# Brain-PCB_Master.net
KiCad netlist of a schematic drawn in Altium Designer
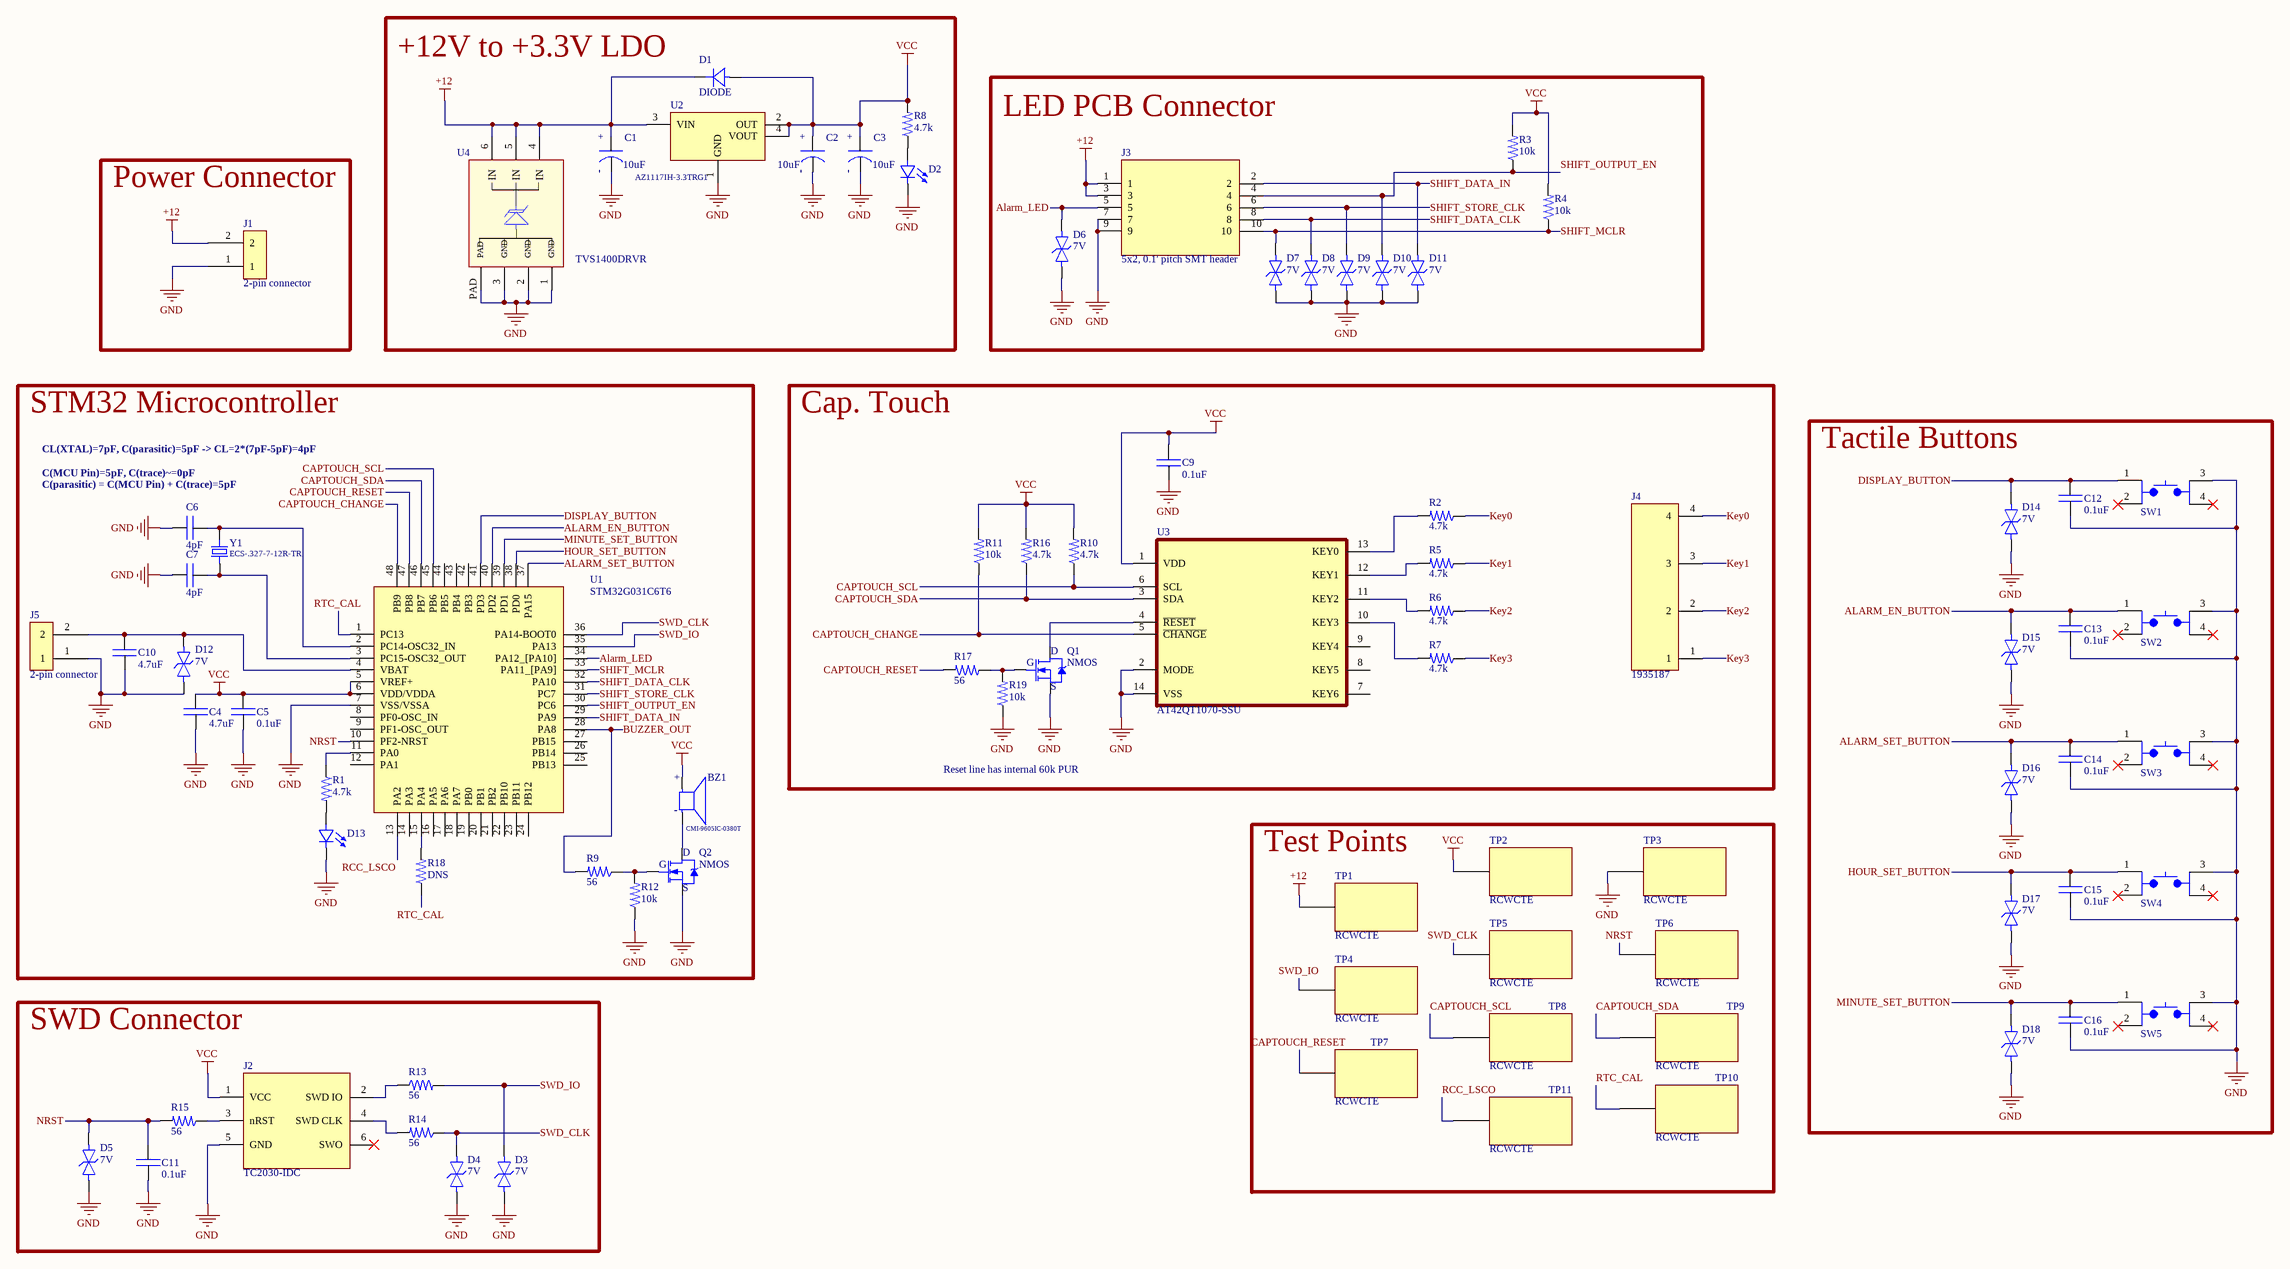
[diagram p0: Brain-PCB_Master.SchDoc]

(export (version "E")
  (design (tool "Eeschema 10.0.6"))
  (components
    (comp (ref "BZ1")
      (value "CMI-9605IC-0380T")
      (footprint "sinking-clock:CUI_CMI-9605IC-0380T")
      (description "MAGNETIC BUZZER INDICATOR")
      (fields (field (name "MFR") "CUI Devices"))
      (libsource (lib "sinking-clock") (part "CMI-9605IC-0380T"))
    )
    (comp (ref "C1")
      (value "10uF")
      (footprint "sinking-clock:CAP_CAN_POLY")
      (description "Capacitor")
      (fields (field (name "MFR") "Würth Elektronik") (field (name "Comment") "CAP"))
      (libsource (lib "sinking-clock") (part "CAP - POLARIZED"))
    )
    (comp (ref "C2")
      (value "10uF")
      (footprint "sinking-clock:CAP_CAN_POLY")
      (description "Capacitor")
      (fields (field (name "MFR") "Würth Elektronik") (field (name "Comment") "CAP"))
      (libsource (lib "sinking-clock") (part "CAP - POLARIZED"))
    )
    (comp (ref "C3")
      (value "10uF")
      (footprint "sinking-clock:CAP_CAN_POLY")
      (description "Capacitor")
      (fields (field (name "MFR") "Würth Elektronik") (field (name "Comment") "CAP"))
      (libsource (lib "sinking-clock") (part "CAP - POLARIZED"))
    )
    (comp (ref "C4")
      (value "4.7uF")
      (footprint "sinking-clock:0402C")
      (description "Capacitor")
      (fields (field (name "MFR") "Samsung Electro-Mechanics") (field (name "Comment") "CAP"))
      (libsource (lib "sinking-clock") (part "CAP"))
    )
    (comp (ref "C5")
      (value "0.1uF")
      (footprint "sinking-clock:0402C")
      (description "Capacitor")
      (fields (field (name "MFR") "Samsung Electro-Mechanics") (field (name "Comment") "CAP"))
      (libsource (lib "sinking-clock") (part "CAP"))
    )
    (comp (ref "C6")
      (value "4pF")
      (footprint "sinking-clock:0402C")
      (description "Capacitor")
      (fields (field (name "MFR") "YAGEO") (field (name "Comment") "CAP"))
      (libsource (lib "sinking-clock") (part "CAP"))
    )
    (comp (ref "C7")
      (value "4pF")
      (footprint "sinking-clock:0402C")
      (description "Capacitor")
      (fields (field (name "MFR") "YAGEO") (field (name "Comment") "CAP"))
      (libsource (lib "sinking-clock") (part "CAP"))
    )
    (comp (ref "C9")
      (value "0.1uF")
      (footprint "sinking-clock:0402C")
      (description "Capacitor")
      (fields (field (name "MFR") "Samsung Electro-Mechanics") (field (name "Comment") "CAP"))
      (libsource (lib "sinking-clock") (part "CAP"))
    )
    (comp (ref "C10")
      (value "4.7uF")
      (footprint "sinking-clock:0402C")
      (description "Capacitor")
      (fields (field (name "MFR") "Samsung Electro-Mechanics") (field (name "Comment") "CAP"))
      (libsource (lib "sinking-clock") (part "CAP"))
    )
    (comp (ref "C11")
      (value "0.1uF")
      (footprint "sinking-clock:0402C")
      (description "Capacitor")
      (fields (field (name "MFR") "Samsung Electro-Mechanics") (field (name "Comment") "CAP"))
      (libsource (lib "sinking-clock") (part "CAP"))
    )
    (comp (ref "C12")
      (value "0.1uF")
      (footprint "sinking-clock:0402C")
      (description "Capacitor")
      (fields (field (name "MFR") "Samsung Electro-Mechanics") (field (name "Comment") "CAP"))
      (libsource (lib "sinking-clock") (part "CAP"))
    )
    (comp (ref "C13")
      (value "0.1uF")
      (footprint "sinking-clock:0402C")
      (description "Capacitor")
      (fields (field (name "MFR") "Samsung Electro-Mechanics") (field (name "Comment") "CAP"))
      (libsource (lib "sinking-clock") (part "CAP"))
    )
    (comp (ref "C14")
      (value "0.1uF")
      (footprint "sinking-clock:0402C")
      (description "Capacitor")
      (fields (field (name "MFR") "Samsung Electro-Mechanics") (field (name "Comment") "CAP"))
      (libsource (lib "sinking-clock") (part "CAP"))
    )
    (comp (ref "C15")
      (value "0.1uF")
      (footprint "sinking-clock:0402C")
      (description "Capacitor")
      (fields (field (name "MFR") "Samsung Electro-Mechanics") (field (name "Comment") "CAP"))
      (libsource (lib "sinking-clock") (part "CAP"))
    )
    (comp (ref "C16")
      (value "0.1uF")
      (footprint "sinking-clock:0402C")
      (description "Capacitor")
      (fields (field (name "MFR") "Samsung Electro-Mechanics") (field (name "Comment") "CAP"))
      (libsource (lib "sinking-clock") (part "CAP"))
    )
    (comp (ref "D1")
      (value "DIODE")
      (footprint "sinking-clock:DO-214AC")
      (description "DIODE GEN PURP")
      (fields (field (name "MFR") "Micro Commercial Co"))
      (libsource (lib "sinking-clock") (part "DIODE"))
    )
    (comp (ref "D2")
      (value "LED - single")
      (footprint "sinking-clock:LED - 0603")
      (description "LED")
      (fields (field (name "MFR") "Dialight"))
      (libsource (lib "sinking-clock") (part "LED - single"))
    )
    (comp (ref "D3")
      (value "7V")
      (footprint "sinking-clock:DESD3V3S1BL-7B")
      (fields (field (name "MFR") "Diodes Incorporated"))
      (libsource (lib "sinking-clock") (part "TVS Diode Bi"))
    )
    (comp (ref "D4")
      (value "7V")
      (footprint "sinking-clock:DESD3V3S1BL-7B")
      (fields (field (name "MFR") "Diodes Incorporated"))
      (libsource (lib "sinking-clock") (part "TVS Diode Bi"))
    )
    (comp (ref "D5")
      (value "7V")
      (footprint "sinking-clock:DESD3V3S1BL-7B")
      (fields (field (name "MFR") "Diodes Incorporated"))
      (libsource (lib "sinking-clock") (part "TVS Diode Bi"))
    )
    (comp (ref "D6")
      (value "7V")
      (footprint "sinking-clock:DESD3V3S1BL-7B")
      (fields (field (name "MFR") "Diodes Incorporated"))
      (libsource (lib "sinking-clock") (part "TVS Diode Bi"))
    )
    (comp (ref "D7")
      (value "7V")
      (footprint "sinking-clock:DESD3V3S1BL-7B")
      (fields (field (name "MFR") "Diodes Incorporated"))
      (libsource (lib "sinking-clock") (part "TVS Diode Bi"))
    )
    (comp (ref "D8")
      (value "7V")
      (footprint "sinking-clock:DESD3V3S1BL-7B")
      (fields (field (name "MFR") "Diodes Incorporated"))
      (libsource (lib "sinking-clock") (part "TVS Diode Bi"))
    )
    (comp (ref "D9")
      (value "7V")
      (footprint "sinking-clock:DESD3V3S1BL-7B")
      (fields (field (name "MFR") "Diodes Incorporated"))
      (libsource (lib "sinking-clock") (part "TVS Diode Bi"))
    )
    (comp (ref "D10")
      (value "7V")
      (footprint "sinking-clock:DESD3V3S1BL-7B")
      (fields (field (name "MFR") "Diodes Incorporated"))
      (libsource (lib "sinking-clock") (part "TVS Diode Bi"))
    )
    (comp (ref "D11")
      (value "7V")
      (footprint "sinking-clock:DESD3V3S1BL-7B")
      (fields (field (name "MFR") "Diodes Incorporated"))
      (libsource (lib "sinking-clock") (part "TVS Diode Bi"))
    )
    (comp (ref "D12")
      (value "7V")
      (footprint "sinking-clock:DESD3V3S1BL-7B")
      (fields (field (name "MFR") "Diodes Incorporated"))
      (libsource (lib "sinking-clock") (part "TVS Diode Bi"))
    )
    (comp (ref "D13")
      (value "LED - single")
      (footprint "sinking-clock:LED - 0603")
      (description "LED")
      (fields (field (name "MFR") "Dialight"))
      (libsource (lib "sinking-clock") (part "LED - single"))
    )
    (comp (ref "D14")
      (value "7V")
      (footprint "sinking-clock:DESD3V3S1BL-7B")
      (fields (field (name "MFR") "Diodes Incorporated"))
      (libsource (lib "sinking-clock") (part "TVS Diode Bi"))
    )
    (comp (ref "D15")
      (value "7V")
      (footprint "sinking-clock:DESD3V3S1BL-7B")
      (fields (field (name "MFR") "Diodes Incorporated"))
      (libsource (lib "sinking-clock") (part "TVS Diode Bi"))
    )
    (comp (ref "D16")
      (value "7V")
      (footprint "sinking-clock:DESD3V3S1BL-7B")
      (fields (field (name "MFR") "Diodes Incorporated"))
      (libsource (lib "sinking-clock") (part "TVS Diode Bi"))
    )
    (comp (ref "D17")
      (value "7V")
      (footprint "sinking-clock:DESD3V3S1BL-7B")
      (fields (field (name "MFR") "Diodes Incorporated"))
      (libsource (lib "sinking-clock") (part "TVS Diode Bi"))
    )
    (comp (ref "D18")
      (value "7V")
      (footprint "sinking-clock:DESD3V3S1BL-7B")
      (fields (field (name "MFR") "Diodes Incorporated"))
      (libsource (lib "sinking-clock") (part "TVS Diode Bi"))
    )
    (comp (ref "J1")
      (value "2-pin connector")
      (footprint "sinking-clock:CONN_MOLEX_705510001")
      (description "CONN HEADER R/A 2POS 2.54MM")
      (fields (field (name "MFR") "MOLEX"))
      (libsource (lib "") (part "2-pin connector_1"))
    )
    (comp (ref "J2")
      (value "TC2030-IDC")
      (footprint "sinking-clock:TAG CONNECT TC2030IDC - NO 3D MODEL")
      (description "\"Plug of Nails\" POGO Pin connector")
      (fields (field (name "MFR") "Tag-Connect"))
      (libsource (lib "sinking-clock") (part "TC2030-IDC"))
    )
    (comp (ref "J3")
      (value "5x2, 0.1' pitch SMT header")
      (footprint "sinking-clock:5x2, 0.1' pitch SMT header")
      (description "CONN HEADER SMD 10POS 2.54MM")
      (fields (field (name "MFR") "CNC Tech"))
      (libsource (lib "sinking-clock") (part "5x2, 0.1' pitch SMT header"))
    )
    (comp (ref "J4")
      (value "1935187")
      (footprint "sinking-clock:1935187")
      (description "Fixed Terminal Blocks PT 1.5/4-5.0-H")
      (fields (field (name "MFR") "Phoenix Contact"))
      (libsource (lib "sinking-clock") (part "SCREW CONN 4 POS"))
    )
    (comp (ref "J5")
      (value "2-pin connector")
      (footprint "sinking-clock:CONN_MOLEX_705510001")
      (description "CONN HEADER R/A 2POS 2.54MM")
      (fields (field (name "MFR") "MOLEX"))
      (libsource (lib "sinking-clock") (part "2-pin connector"))
    )
    (comp (ref "Q1")
      (value "NMOS")
      (footprint "sinking-clock:SOT-23")
      (description "N-Channel MOSFET")
      (fields (field (name "MFR") "Diodes Incorporated"))
      (libsource (lib "sinking-clock") (part "NMOS"))
    )
    (comp (ref "Q2")
      (value "NMOS")
      (footprint "sinking-clock:SOT-23")
      (description "N-Channel MOSFET")
      (fields (field (name "MFR") "Diodes Incorporated"))
      (libsource (lib "sinking-clock") (part "NMOS"))
    )
    (comp (ref "R1")
      (value "4.7k")
      (footprint "sinking-clock:0402R")
      (description "Resistor")
      (fields (field (name "MFR") "YAGEO") (field (name "Comment") "RES"))
      (libsource (lib "sinking-clock") (part "RES"))
    )
    (comp (ref "R2")
      (value "4.7k")
      (footprint "sinking-clock:0402R")
      (description "Resistor")
      (fields (field (name "MFR") "YAGEO") (field (name "Comment") "RES"))
      (libsource (lib "sinking-clock") (part "RES"))
    )
    (comp (ref "R3")
      (value "10k")
      (footprint "sinking-clock:0402R")
      (description "Resistor")
      (fields (field (name "MFR") "YAGEO") (field (name "Comment") "RES"))
      (libsource (lib "sinking-clock") (part "RES"))
    )
    (comp (ref "R4")
      (value "10k")
      (footprint "sinking-clock:0402R")
      (description "Resistor")
      (fields (field (name "MFR") "YAGEO") (field (name "Comment") "RES"))
      (libsource (lib "sinking-clock") (part "RES"))
    )
    (comp (ref "R5")
      (value "4.7k")
      (footprint "sinking-clock:0402R")
      (description "Resistor")
      (fields (field (name "MFR") "YAGEO") (field (name "Comment") "RES"))
      (libsource (lib "sinking-clock") (part "RES"))
    )
    (comp (ref "R6")
      (value "4.7k")
      (footprint "sinking-clock:0402R")
      (description "Resistor")
      (fields (field (name "MFR") "YAGEO") (field (name "Comment") "RES"))
      (libsource (lib "sinking-clock") (part "RES"))
    )
    (comp (ref "R7")
      (value "4.7k")
      (footprint "sinking-clock:0402R")
      (description "Resistor")
      (fields (field (name "MFR") "YAGEO") (field (name "Comment") "RES"))
      (libsource (lib "sinking-clock") (part "RES"))
    )
    (comp (ref "R8")
      (value "4.7k")
      (footprint "sinking-clock:0402R")
      (description "Resistor")
      (fields (field (name "MFR") "YAGEO") (field (name "Comment") "RES"))
      (libsource (lib "sinking-clock") (part "RES"))
    )
    (comp (ref "R9")
      (value "56")
      (footprint "sinking-clock:0402R")
      (description "Resistor")
      (fields (field (name "MFR") "YAGEO") (field (name "Comment") "RES"))
      (libsource (lib "sinking-clock") (part "RES"))
    )
    (comp (ref "R10")
      (value "4.7k")
      (footprint "sinking-clock:0402R")
      (description "Resistor")
      (fields (field (name "MFR") "YAGEO") (field (name "Comment") "RES"))
      (libsource (lib "sinking-clock") (part "RES"))
    )
    (comp (ref "R11")
      (value "10k")
      (footprint "sinking-clock:0402R")
      (description "Resistor")
      (fields (field (name "MFR") "YAGEO") (field (name "Comment") "RES"))
      (libsource (lib "sinking-clock") (part "RES"))
    )
    (comp (ref "R12")
      (value "10k")
      (footprint "sinking-clock:0402R")
      (description "Resistor")
      (fields (field (name "MFR") "YAGEO") (field (name "Comment") "RES"))
      (libsource (lib "sinking-clock") (part "RES"))
    )
    (comp (ref "R13")
      (value "56")
      (footprint "sinking-clock:0402R")
      (description "Resistor")
      (fields (field (name "MFR") "YAGEO") (field (name "Comment") "RES"))
      (libsource (lib "sinking-clock") (part "RES"))
    )
    (comp (ref "R14")
      (value "56")
      (footprint "sinking-clock:0402R")
      (description "Resistor")
      (fields (field (name "MFR") "YAGEO") (field (name "Comment") "RES"))
      (libsource (lib "sinking-clock") (part "RES"))
    )
    (comp (ref "R15")
      (value "56")
      (footprint "sinking-clock:0402R")
      (description "Resistor")
      (fields (field (name "MFR") "YAGEO") (field (name "Comment") "RES"))
      (libsource (lib "sinking-clock") (part "RES"))
    )
    (comp (ref "R16")
      (value "4.7k")
      (footprint "sinking-clock:0402R")
      (description "Resistor")
      (fields (field (name "MFR") "YAGEO") (field (name "Comment") "RES"))
      (libsource (lib "sinking-clock") (part "RES"))
    )
    (comp (ref "R17")
      (value "56")
      (footprint "sinking-clock:0402R")
      (description "Resistor")
      (fields (field (name "MFR") "YAGEO") (field (name "Comment") "RES"))
      (libsource (lib "sinking-clock") (part "RES"))
    )
    (comp (ref "R18")
      (value "DNS")
      (footprint "sinking-clock:0402R")
      (description "Resistor")
      (fields (field (name "Comment") "RES"))
      (libsource (lib "sinking-clock") (part "RES"))
    )
    (comp (ref "R19")
      (value "10k")
      (footprint "sinking-clock:0402R")
      (description "Resistor")
      (fields (field (name "MFR") "YAGEO") (field (name "Comment") "RES"))
      (libsource (lib "sinking-clock") (part "RES"))
    )
    (comp (ref "SW1")
      (value "SPDT SMT Tactile Push Button Switch")
      (footprint "sinking-clock:TL3301BF160QGTUBE")
      (description "Tactile Push Button Switch, Gull Wing Lead, 9.5mm contact height")
      (fields (field (name "MFR") "E-Switch"))
      (libsource (lib "sinking-clock") (part "SPDT SMT Tactile Push Button Switch"))
    )
    (comp (ref "SW2")
      (value "SPDT SMT Tactile Push Button Switch")
      (footprint "sinking-clock:TL3301BF160QGTUBE")
      (description "Tactile Push Button Switch, Gull Wing Lead, 9.5mm contact height")
      (fields (field (name "MFR") "E-Switch"))
      (libsource (lib "sinking-clock") (part "SPDT SMT Tactile Push Button Switch"))
    )
    (comp (ref "SW3")
      (value "SPDT SMT Tactile Push Button Switch")
      (footprint "sinking-clock:TL3301BF160QGTUBE")
      (description "Tactile Push Button Switch, Gull Wing Lead, 9.5mm contact height")
      (fields (field (name "MFR") "E-Switch"))
      (libsource (lib "sinking-clock") (part "SPDT SMT Tactile Push Button Switch"))
    )
    (comp (ref "SW4")
      (value "SPDT SMT Tactile Push Button Switch")
      (footprint "sinking-clock:TL3301BF160QGTUBE")
      (description "Tactile Push Button Switch, Gull Wing Lead, 9.5mm contact height")
      (fields (field (name "MFR") "E-Switch"))
      (libsource (lib "sinking-clock") (part "SPDT SMT Tactile Push Button Switch"))
    )
    (comp (ref "SW5")
      (value "SPDT SMT Tactile Push Button Switch")
      (footprint "sinking-clock:TL3301BF160QGTUBE")
      (description "Tactile Push Button Switch, Gull Wing Lead, 9.5mm contact height")
      (fields (field (name "MFR") "E-Switch"))
      (libsource (lib "sinking-clock") (part "SPDT SMT Tactile Push Button Switch"))
    )
    (comp (ref "TP1")
      (value "RCWCTE")
      (footprint "sinking-clock:RCWCTE")
      (description "Test Point, Surface Mount")
      (fields (field (name "MFR") "KOA Speer Electronics, Inc."))
      (libsource (lib "sinking-clock") (part "Test Point"))
    )
    (comp (ref "TP2")
      (value "RCWCTE")
      (footprint "sinking-clock:RCWCTE")
      (description "Test Point, Surface Mount")
      (fields (field (name "MFR") "KOA Speer Electronics, Inc."))
      (libsource (lib "sinking-clock") (part "Test Point"))
    )
    (comp (ref "TP3")
      (value "RCWCTE")
      (footprint "sinking-clock:RCWCTE")
      (description "Test Point, Surface Mount")
      (fields (field (name "MFR") "KOA Speer Electronics, Inc."))
      (libsource (lib "sinking-clock") (part "Test Point"))
    )
    (comp (ref "TP4")
      (value "RCWCTE")
      (footprint "sinking-clock:RCWCTE")
      (description "Test Point, Surface Mount")
      (fields (field (name "MFR") "KOA Speer Electronics, Inc."))
      (libsource (lib "sinking-clock") (part "Test Point"))
    )
    (comp (ref "TP5")
      (value "RCWCTE")
      (footprint "sinking-clock:RCWCTE")
      (description "Test Point, Surface Mount")
      (fields (field (name "MFR") "KOA Speer Electronics, Inc."))
      (libsource (lib "sinking-clock") (part "Test Point"))
    )
    (comp (ref "TP6")
      (value "RCWCTE")
      (footprint "sinking-clock:RCWCTE")
      (description "Test Point, Surface Mount")
      (fields (field (name "MFR") "KOA Speer Electronics, Inc."))
      (libsource (lib "sinking-clock") (part "Test Point"))
    )
    (comp (ref "TP7")
      (value "RCWCTE")
      (footprint "sinking-clock:RCWCTE")
      (description "Test Point, Surface Mount")
      (fields (field (name "MFR") "KOA Speer Electronics, Inc."))
      (libsource (lib "sinking-clock") (part "Test Point"))
    )
    (comp (ref "TP8")
      (value "RCWCTE")
      (footprint "sinking-clock:RCWCTE")
      (description "Test Point, Surface Mount")
      (fields (field (name "MFR") "KOA Speer Electronics, Inc."))
      (libsource (lib "sinking-clock") (part "Test Point"))
    )
    (comp (ref "TP9")
      (value "RCWCTE")
      (footprint "sinking-clock:RCWCTE")
      (description "Test Point, Surface Mount")
      (fields (field (name "MFR") "KOA Speer Electronics, Inc."))
      (libsource (lib "sinking-clock") (part "Test Point"))
    )
    (comp (ref "TP10")
      (value "RCWCTE")
      (footprint "sinking-clock:RCWCTE")
      (description "Test Point, Surface Mount")
      (fields (field (name "MFR") "KOA Speer Electronics, Inc."))
      (libsource (lib "sinking-clock") (part "Test Point"))
    )
    (comp (ref "TP11")
      (value "RCWCTE")
      (footprint "sinking-clock:RCWCTE")
      (description "Test Point, Surface Mount")
      (fields (field (name "MFR") "KOA Speer Electronics, Inc."))
      (libsource (lib "sinking-clock") (part "Test Point"))
    )
    (comp (ref "U1")
      (value "STM32G031C6T6")
      (footprint "sinking-clock:48-LQFP")
      (fields (field (name "MFR") "STMicroelectronics"))
      (libsource (lib "sinking-clock") (part "STM32G031C6T6"))
    )
    (comp (ref "U2")
      (value "AZ1117IH-3.3TRG1")
      (footprint "sinking-clock:SOT-223-3")
      (description "IC REG LINEAR 3.3V 1A SOT223")
      (fields (field (name "MFR") "Diodes Incorporated"))
      (libsource (lib "sinking-clock") (part "AZ1117IH-3.3TRG1"))
    )
    (comp (ref "U3")
      (value "AT42QT1070-SSU")
      (footprint "sinking-clock:14-SOIC")
      (description "Capacitive Touch Buttons 14-SOIC")
      (fields (field (name "MFR") "Microchip"))
      (libsource (lib "sinking-clock") (part "AT42QT1070-SSU"))
    )
    (comp (ref "U4")
      (value "TVS1400DRVR")
      (footprint "sinking-clock:6-WDFN-EP")
      (description "UNIDIR  PRECISION SURGE DIODE")
      (fields (field (name "MFR") "Texas Instruments"))
      (libsource (lib "sinking-clock") (part "TVS1400DRVR"))
    )
    (comp (ref "Y1")
      (value "ECS-.327-7-12R-TR")
      (footprint "sinking-clock:ECS-.327-12.5-12R-TR")
      (description "SMD Tuning Fork Crystal")
      (fields (field (name "MFR") "ECS Inc."))
      (libsource (lib "sinking-clock") (part "ECS-.327-7-12R-TR"))
    )
  )
  (nets
    (net (code "1") (name "+12") (class "Default")
      (node (ref "C1") (pin "1") (pinfunction "1_1") (pintype "passive"))
      (node (ref "D1") (pin "K") (pinfunction "K_K") (pintype "passive"))
      (node (ref "J1") (pin "2") (pinfunction "2_2") (pintype "passive"))
      (node (ref "J3") (pin "1") (pinfunction "1_1") (pintype "passive"))
      (node (ref "J3") (pin "3") (pinfunction "3_3") (pintype "passive"))
      (node (ref "TP1") (pin "1") (pinfunction "0_1") (pintype "passive"))
      (node (ref "U2") (pin "3") (pinfunction "VIN_3") (pintype "passive"))
      (node (ref "U4") (pin "4") (pinfunction "IN_4") (pintype "passive"))
      (node (ref "U4") (pin "5") (pinfunction "IN_5") (pintype "passive"))
      (node (ref "U4") (pin "6") (pinfunction "IN_6") (pintype "passive"))
    )
    (net (code "2") (name "/ALARM_EN_BUTTON") (class "Default")
      (node (ref "C13") (pin "2") (pinfunction "2_2") (pintype "passive"))
      (node (ref "D15") (pin "1") (pinfunction "1_1") (pintype "passive"))
      (node (ref "SW2") (pin "1") (pinfunction "1_1") (pintype "passive"))
      (node (ref "U1") (pin "40") (pinfunction "PD2_40") (pintype "passive"))
    )
    (net (code "3") (name "/ALARM_SET_BUTTON") (class "Default")
      (node (ref "C14") (pin "2") (pinfunction "2_2") (pintype "passive"))
      (node (ref "D16") (pin "1") (pinfunction "1_1") (pintype "passive"))
      (node (ref "SW3") (pin "1") (pinfunction "1_1") (pintype "passive"))
      (node (ref "U1") (pin "37") (pinfunction "PA15_37") (pintype "passive"))
    )
    (net (code "4") (name "/Alarm_LED") (class "Default")
      (node (ref "D6") (pin "1") (pinfunction "1_1") (pintype "passive"))
      (node (ref "J3") (pin "5") (pinfunction "5_5") (pintype "passive"))
      (node (ref "U1") (pin "34") (pinfunction "PA12_[PA10]_34") (pintype "passive"))
    )
    (net (code "5") (name "/BUZZER_OUT") (class "Default")
      (node (ref "R9") (pin "2") (pinfunction "2_2") (pintype "passive"))
      (node (ref "U1") (pin "28") (pinfunction "PA8_28") (pintype "passive"))
    )
    (net (code "6") (name "/CAPTOUCH_CHANGE") (class "Default")
      (node (ref "R11") (pin "1") (pinfunction "1_1") (pintype "passive"))
      (node (ref "U1") (pin "48") (pinfunction "PB9_48") (pintype "passive"))
      (node (ref "U3") (pin "5") (pinfunction "~{CHANGE}_5") (pintype "passive"))
    )
    (net (code "7") (name "/CAPTOUCH_RESET") (class "Default")
      (node (ref "R17") (pin "2") (pinfunction "2_2") (pintype "passive"))
      (node (ref "TP7") (pin "1") (pinfunction "0_1") (pintype "passive"))
      (node (ref "U1") (pin "47") (pinfunction "PB8_47") (pintype "passive"))
    )
    (net (code "8") (name "/CAPTOUCH_SCL") (class "Default")
      (node (ref "R10") (pin "1") (pinfunction "1_1") (pintype "passive"))
      (node (ref "TP8") (pin "1") (pinfunction "0_1") (pintype "passive"))
      (node (ref "U1") (pin "45") (pinfunction "PB6_45") (pintype "passive"))
      (node (ref "U3") (pin "6") (pinfunction "SCL_6") (pintype "passive"))
    )
    (net (code "9") (name "/CAPTOUCH_SDA") (class "Default")
      (node (ref "R16") (pin "1") (pinfunction "1_1") (pintype "passive"))
      (node (ref "TP9") (pin "1") (pinfunction "0_1") (pintype "passive"))
      (node (ref "U1") (pin "46") (pinfunction "PB7_46") (pintype "passive"))
      (node (ref "U3") (pin "3") (pinfunction "SDA_3") (pintype "passive"))
    )
    (net (code "10") (name "/DISPLAY_BUTTON") (class "Default")
      (node (ref "C12") (pin "2") (pinfunction "2_2") (pintype "passive"))
      (node (ref "D14") (pin "1") (pinfunction "1_1") (pintype "passive"))
      (node (ref "SW1") (pin "1") (pinfunction "1_1") (pintype "passive"))
      (node (ref "U1") (pin "41") (pinfunction "PD3_41") (pintype "passive"))
    )
    (net (code "11") (name "/HOUR_SET_BUTTON") (class "Default")
      (node (ref "C15") (pin "2") (pinfunction "2_2") (pintype "passive"))
      (node (ref "D17") (pin "1") (pinfunction "1_1") (pintype "passive"))
      (node (ref "SW4") (pin "1") (pinfunction "1_1") (pintype "passive"))
      (node (ref "U1") (pin "38") (pinfunction "PD0_38") (pintype "passive"))
    )
    (net (code "12") (name "/Key0") (class "Default")
      (node (ref "J4") (pin "4") (pinfunction "4_4") (pintype "passive"))
      (node (ref "R2") (pin "1") (pinfunction "1_1") (pintype "passive"))
    )
    (net (code "13") (name "/Key1") (class "Default")
      (node (ref "J4") (pin "3") (pinfunction "3_3") (pintype "passive"))
      (node (ref "R5") (pin "1") (pinfunction "1_1") (pintype "passive"))
    )
    (net (code "14") (name "/Key2") (class "Default")
      (node (ref "J4") (pin "2") (pinfunction "2_2") (pintype "passive"))
      (node (ref "R6") (pin "1") (pinfunction "1_1") (pintype "passive"))
    )
    (net (code "15") (name "/Key3") (class "Default")
      (node (ref "J4") (pin "1") (pinfunction "1_1") (pintype "passive"))
      (node (ref "R7") (pin "1") (pinfunction "1_1") (pintype "passive"))
    )
    (net (code "16") (name "/MINUTE_SET_BUTTON") (class "Default")
      (node (ref "C16") (pin "2") (pinfunction "2_2") (pintype "passive"))
      (node (ref "D18") (pin "1") (pinfunction "1_1") (pintype "passive"))
      (node (ref "SW5") (pin "1") (pinfunction "1_1") (pintype "passive"))
      (node (ref "U1") (pin "39") (pinfunction "PD1_39") (pintype "passive"))
    )
    (net (code "17") (name "/NRST") (class "Default")
      (node (ref "C11") (pin "2") (pinfunction "2_2") (pintype "passive"))
      (node (ref "D5") (pin "1") (pinfunction "1_1") (pintype "passive"))
      (node (ref "R15") (pin "2") (pinfunction "2_2") (pintype "passive"))
      (node (ref "TP6") (pin "1") (pinfunction "0_1") (pintype "passive"))
      (node (ref "U1") (pin "10") (pinfunction "PF2-NRST_10") (pintype "passive"))
    )
    (net (code "18") (name "/RCC_LSCO") (class "Default")
      (node (ref "TP11") (pin "1") (pinfunction "0_1") (pintype "passive"))
      (node (ref "U1") (pin "13") (pinfunction "PA2_13") (pintype "passive"))
    )
    (net (code "19") (name "/RTC_CAL") (class "Default")
      (node (ref "R18") (pin "1") (pinfunction "1_1") (pintype "passive"))
      (node (ref "TP10") (pin "1") (pinfunction "0_1") (pintype "passive"))
      (node (ref "U1") (pin "1") (pinfunction "PC13_1") (pintype "passive"))
    )
    (net (code "20") (name "/SHIFT_DATA_CLK") (class "Default")
      (node (ref "D8") (pin "1") (pinfunction "1_1") (pintype "passive"))
      (node (ref "J3") (pin "8") (pinfunction "8_8") (pintype "passive"))
      (node (ref "U1") (pin "32") (pinfunction "PA10_32") (pintype "passive"))
    )
    (net (code "21") (name "/SHIFT_DATA_IN") (class "Default")
      (node (ref "D11") (pin "1") (pinfunction "1_1") (pintype "passive"))
      (node (ref "J3") (pin "2") (pinfunction "2_2") (pintype "passive"))
      (node (ref "U1") (pin "29") (pinfunction "PA9_29") (pintype "passive"))
    )
    (net (code "22") (name "/SHIFT_MCLR") (class "Default")
      (node (ref "D7") (pin "1") (pinfunction "1_1") (pintype "passive"))
      (node (ref "J3") (pin "10") (pinfunction "10_10") (pintype "passive"))
      (node (ref "R4") (pin "1") (pinfunction "1_1") (pintype "passive"))
      (node (ref "U1") (pin "33") (pinfunction "PA11_[PA9]_33") (pintype "passive"))
    )
    (net (code "23") (name "/SHIFT_OUTPUT_EN") (class "Default")
      (node (ref "D10") (pin "1") (pinfunction "1_1") (pintype "passive"))
      (node (ref "J3") (pin "4") (pinfunction "4_4") (pintype "passive"))
      (node (ref "R3") (pin "1") (pinfunction "1_1") (pintype "passive"))
      (node (ref "U1") (pin "30") (pinfunction "PC6_30") (pintype "passive"))
    )
    (net (code "24") (name "/SHIFT_STORE_CLK") (class "Default")
      (node (ref "D9") (pin "1") (pinfunction "1_1") (pintype "passive"))
      (node (ref "J3") (pin "6") (pinfunction "6_6") (pintype "passive"))
      (node (ref "U1") (pin "31") (pinfunction "PC7_31") (pintype "passive"))
    )
    (net (code "25") (name "/SWD_CLK") (class "Default")
      (node (ref "D4") (pin "1") (pinfunction "1_1") (pintype "passive"))
      (node (ref "R14") (pin "1") (pinfunction "1_1") (pintype "passive"))
      (node (ref "TP5") (pin "1") (pinfunction "0_1") (pintype "passive"))
      (node (ref "U1") (pin "36") (pinfunction "PA14-BOOT0_36") (pintype "passive"))
    )
    (net (code "26") (name "/SWD_IO") (class "Default")
      (node (ref "D3") (pin "1") (pinfunction "1_1") (pintype "passive"))
      (node (ref "R13") (pin "2") (pinfunction "2_2") (pintype "passive"))
      (node (ref "TP4") (pin "1") (pinfunction "0_1") (pintype "passive"))
      (node (ref "U1") (pin "35") (pinfunction "PA13_35") (pintype "passive"))
    )
    (net (code "27") (name "GND") (class "Default")
      (node (ref "C1") (pin "2") (pinfunction "2_2") (pintype "passive"))
      (node (ref "C10") (pin "1") (pinfunction "1_1") (pintype "passive"))
      (node (ref "C11") (pin "1") (pinfunction "1_1") (pintype "passive"))
      (node (ref "C12") (pin "1") (pinfunction "1_1") (pintype "passive"))
      (node (ref "C13") (pin "1") (pinfunction "1_1") (pintype "passive"))
      (node (ref "C14") (pin "1") (pinfunction "1_1") (pintype "passive"))
      (node (ref "C15") (pin "1") (pinfunction "1_1") (pintype "passive"))
      (node (ref "C16") (pin "1") (pinfunction "1_1") (pintype "passive"))
      (node (ref "C2") (pin "2") (pinfunction "2_2") (pintype "passive"))
      (node (ref "C3") (pin "2") (pinfunction "2_2") (pintype "passive"))
      (node (ref "C4") (pin "1") (pinfunction "1_1") (pintype "passive"))
      (node (ref "C5") (pin "1") (pinfunction "1_1") (pintype "passive"))
      (node (ref "C6") (pin "1") (pinfunction "1_1") (pintype "passive"))
      (node (ref "C7") (pin "1") (pinfunction "1_1") (pintype "passive"))
      (node (ref "C9") (pin "1") (pinfunction "1_1") (pintype "passive"))
      (node (ref "D10") (pin "2") (pinfunction "2_2") (pintype "passive"))
      (node (ref "D11") (pin "2") (pinfunction "2_2") (pintype "passive"))
      (node (ref "D12") (pin "2") (pinfunction "2_2") (pintype "passive"))
      (node (ref "D13") (pin "2") (pinfunction "C_2") (pintype "passive"))
      (node (ref "D14") (pin "2") (pinfunction "2_2") (pintype "passive"))
      (node (ref "D15") (pin "2") (pinfunction "2_2") (pintype "passive"))
      (node (ref "D16") (pin "2") (pinfunction "2_2") (pintype "passive"))
      (node (ref "D17") (pin "2") (pinfunction "2_2") (pintype "passive"))
      (node (ref "D18") (pin "2") (pinfunction "2_2") (pintype "passive"))
      (node (ref "D2") (pin "2") (pinfunction "C_2") (pintype "passive"))
      (node (ref "D3") (pin "2") (pinfunction "2_2") (pintype "passive"))
      (node (ref "D4") (pin "2") (pinfunction "2_2") (pintype "passive"))
      (node (ref "D5") (pin "2") (pinfunction "2_2") (pintype "passive"))
      (node (ref "D6") (pin "2") (pinfunction "2_2") (pintype "passive"))
      (node (ref "D7") (pin "2") (pinfunction "2_2") (pintype "passive"))
      (node (ref "D8") (pin "2") (pinfunction "2_2") (pintype "passive"))
      (node (ref "D9") (pin "2") (pinfunction "2_2") (pintype "passive"))
      (node (ref "J1") (pin "1") (pinfunction "1_1") (pintype "passive"))
      (node (ref "J2") (pin "5") (pinfunction "GND_5") (pintype "passive"))
      (node (ref "J3") (pin "7") (pinfunction "7_7") (pintype "passive"))
      (node (ref "J3") (pin "9") (pinfunction "9_9") (pintype "passive"))
      (node (ref "J5") (pin "1") (pinfunction "1_1") (pintype "passive"))
      (node (ref "Q1") (pin "2") (pinfunction "S_2") (pintype "passive"))
      (node (ref "Q2") (pin "2") (pinfunction "S_2") (pintype "passive"))
      (node (ref "R12") (pin "1") (pinfunction "1_1") (pintype "passive"))
      (node (ref "R19") (pin "1") (pinfunction "1_1") (pintype "passive"))
      (node (ref "SW1") (pin "3") (pinfunction "3_3") (pintype "passive"))
      (node (ref "SW2") (pin "3") (pinfunction "3_3") (pintype "passive"))
      (node (ref "SW3") (pin "3") (pinfunction "3_3") (pintype "passive"))
      (node (ref "SW4") (pin "3") (pinfunction "3_3") (pintype "passive"))
      (node (ref "SW5") (pin "3") (pinfunction "3_3") (pintype "passive"))
      (node (ref "TP3") (pin "1") (pinfunction "0_1") (pintype "passive"))
      (node (ref "U1") (pin "7") (pinfunction "VSS/VSSA_7") (pintype "passive"))
      (node (ref "U2") (pin "1") (pinfunction "GND_1") (pintype "passive"))
      (node (ref "U3") (pin "14") (pinfunction "VSS_14") (pintype "passive"))
      (node (ref "U3") (pin "2") (pinfunction "MODE_2") (pintype "passive"))
      (node (ref "U4") (pin "1") (pinfunction "GND_1") (pintype "passive"))
      (node (ref "U4") (pin "2") (pinfunction "GND_2") (pintype "passive"))
      (node (ref "U4") (pin "3") (pinfunction "GND_3") (pintype "passive"))
      (node (ref "U4") (pin "PAD") (pinfunction "PAD_PAD") (pintype "passive"))
    )
    (net (code "28") (name "Net-(D2-A)") (class "Default")
      (node (ref "D2") (pin "1") (pinfunction "A_1") (pintype "passive"))
      (node (ref "R8") (pin "1") (pinfunction "1_1") (pintype "passive"))
    )
    (net (code "29") (name "Net-(D13-A)") (class "Default")
      (node (ref "D13") (pin "1") (pinfunction "A_1") (pintype "passive"))
      (node (ref "R1") (pin "2") (pinfunction "2_2") (pintype "passive"))
    )
    (net (code "30") (name "Net-(J2-SWD_CLK)") (class "Default")
      (node (ref "J2") (pin "4") (pinfunction "SWD_CLK_4") (pintype "passive"))
      (node (ref "R14") (pin "2") (pinfunction "2_2") (pintype "passive"))
    )
    (net (code "31") (name "Net-(J2-SWD_IO)") (class "Default")
      (node (ref "J2") (pin "2") (pinfunction "SWD_IO_2") (pintype "passive"))
      (node (ref "R13") (pin "1") (pinfunction "1_1") (pintype "passive"))
    )
    (net (code "32") (name "Net-(J2-nRST)") (class "Default")
      (node (ref "J2") (pin "3") (pinfunction "nRST_3") (pintype "passive"))
      (node (ref "R15") (pin "1") (pinfunction "1_1") (pintype "passive"))
    )
    (net (code "33") (name "Net-(Q1-D)") (class "Default")
      (node (ref "Q1") (pin "3") (pinfunction "D_3") (pintype "passive"))
      (node (ref "U3") (pin "4") (pinfunction "~{RESET}_4") (pintype "passive"))
    )
    (net (code "34") (name "Net-(Q1-G)") (class "Default")
      (node (ref "Q1") (pin "1") (pinfunction "G_1") (pintype "passive"))
      (node (ref "R17") (pin "1") (pinfunction "1_1") (pintype "passive"))
      (node (ref "R19") (pin "2") (pinfunction "2_2") (pintype "passive"))
    )
    (net (code "35") (name "Net-(Q2-D)") (class "Default")
      (node (ref "BZ1") (pin "N") (pinfunction "N_N") (pintype "passive"))
      (node (ref "Q2") (pin "3") (pinfunction "D_3") (pintype "passive"))
    )
    (net (code "36") (name "Net-(Q2-G)") (class "Default")
      (node (ref "Q2") (pin "1") (pinfunction "G_1") (pintype "passive"))
      (node (ref "R12") (pin "2") (pinfunction "2_2") (pintype "passive"))
      (node (ref "R9") (pin "1") (pinfunction "1_1") (pintype "passive"))
    )
    (net (code "37") (name "Net-(U1-PA0)") (class "Default")
      (node (ref "R1") (pin "1") (pinfunction "1_1") (pintype "passive"))
      (node (ref "U1") (pin "11") (pinfunction "PA0_11") (pintype "passive"))
    )
    (net (code "38") (name "Net-(U1-PA4)") (class "Default")
      (node (ref "R18") (pin "2") (pinfunction "2_2") (pintype "passive"))
      (node (ref "U1") (pin "15") (pinfunction "PA4_15") (pintype "passive"))
    )
    (net (code "39") (name "Net-(U1-PC14-OSC32_IN)") (class "Default")
      (node (ref "C6") (pin "2") (pinfunction "2_2") (pintype "passive"))
      (node (ref "U1") (pin "2") (pinfunction "PC14-OSC32_IN_2") (pintype "passive"))
      (node (ref "Y1") (pin "2") (pinfunction "2_2") (pintype "passive"))
    )
    (net (code "40") (name "Net-(U1-PC15-OSC32_OUT)") (class "Default")
      (node (ref "C7") (pin "2") (pinfunction "2_2") (pintype "passive"))
      (node (ref "U1") (pin "3") (pinfunction "PC15-OSC32_OUT_3") (pintype "passive"))
      (node (ref "Y1") (pin "1") (pinfunction "1_1") (pintype "passive"))
    )
    (net (code "41") (name "Net-(U1-VBAT)") (class "Default")
      (node (ref "C10") (pin "2") (pinfunction "2_2") (pintype "passive"))
      (node (ref "D12") (pin "1") (pinfunction "1_1") (pintype "passive"))
      (node (ref "J5") (pin "2") (pinfunction "2_2") (pintype "passive"))
      (node (ref "U1") (pin "4") (pinfunction "VBAT_4") (pintype "passive"))
    )
    (net (code "42") (name "Net-(U3-KEY0)") (class "Default")
      (node (ref "R2") (pin "2") (pinfunction "2_2") (pintype "passive"))
      (node (ref "U3") (pin "13") (pinfunction "KEY0_13") (pintype "passive"))
    )
    (net (code "43") (name "Net-(U3-KEY1)") (class "Default")
      (node (ref "R5") (pin "2") (pinfunction "2_2") (pintype "passive"))
      (node (ref "U3") (pin "12") (pinfunction "KEY1_12") (pintype "passive"))
    )
    (net (code "44") (name "Net-(U3-KEY2)") (class "Default")
      (node (ref "R6") (pin "2") (pinfunction "2_2") (pintype "passive"))
      (node (ref "U3") (pin "11") (pinfunction "KEY2_11") (pintype "passive"))
    )
    (net (code "45") (name "Net-(U3-KEY3)") (class "Default")
      (node (ref "R7") (pin "2") (pinfunction "2_2") (pintype "passive"))
      (node (ref "U3") (pin "10") (pinfunction "KEY3_10") (pintype "passive"))
    )
    (net (code "46") (name "VCC") (class "Default")
      (node (ref "BZ1") (pin "P") (pinfunction "P_P") (pintype "passive"))
      (node (ref "C2") (pin "1") (pinfunction "1_1") (pintype "passive"))
      (node (ref "C3") (pin "1") (pinfunction "1_1") (pintype "passive"))
      (node (ref "C4") (pin "2") (pinfunction "2_2") (pintype "passive"))
      (node (ref "C5") (pin "2") (pinfunction "2_2") (pintype "passive"))
      (node (ref "C9") (pin "2") (pinfunction "2_2") (pintype "passive"))
      (node (ref "D1") (pin "A") (pinfunction "A_A") (pintype "passive"))
      (node (ref "J2") (pin "1") (pinfunction "VCC_1") (pintype "passive"))
      (node (ref "R10") (pin "2") (pinfunction "2_2") (pintype "passive"))
      (node (ref "R11") (pin "2") (pinfunction "2_2") (pintype "passive"))
      (node (ref "R16") (pin "2") (pinfunction "2_2") (pintype "passive"))
      (node (ref "R3") (pin "2") (pinfunction "2_2") (pintype "passive"))
      (node (ref "R4") (pin "2") (pinfunction "2_2") (pintype "passive"))
      (node (ref "R8") (pin "2") (pinfunction "2_2") (pintype "passive"))
      (node (ref "TP2") (pin "1") (pinfunction "0_1") (pintype "passive"))
      (node (ref "U1") (pin "5") (pinfunction "VREF+_5") (pintype "passive"))
      (node (ref "U1") (pin "6") (pinfunction "VDD/VDDA_6") (pintype "passive"))
      (node (ref "U2") (pin "2") (pinfunction "OUT_2") (pintype "passive"))
      (node (ref "U2") (pin "4") (pinfunction "VOUT_4") (pintype "passive"))
      (node (ref "U3") (pin "1") (pinfunction "VDD_1") (pintype "passive"))
    )
    (net (code "47") (name "unconnected-(J2-SWO-Pad6)") (class "Default")
      (node (ref "J2") (pin "6") (pinfunction "SWO_6") (pintype "passive+no_connect"))
    )
    (net (code "48") (name "unconnected-(SW1-Pad2)") (class "Default")
      (node (ref "SW1") (pin "2") (pinfunction "2_2") (pintype "passive+no_connect"))
    )
    (net (code "49") (name "unconnected-(SW1-Pad4)") (class "Default")
      (node (ref "SW1") (pin "4") (pinfunction "4_4") (pintype "passive+no_connect"))
    )
    (net (code "50") (name "unconnected-(SW2-Pad2)") (class "Default")
      (node (ref "SW2") (pin "2") (pinfunction "2_2") (pintype "passive+no_connect"))
    )
    (net (code "51") (name "unconnected-(SW2-Pad4)") (class "Default")
      (node (ref "SW2") (pin "4") (pinfunction "4_4") (pintype "passive+no_connect"))
    )
    (net (code "52") (name "unconnected-(SW3-Pad2)") (class "Default")
      (node (ref "SW3") (pin "2") (pinfunction "2_2") (pintype "passive+no_connect"))
    )
    (net (code "53") (name "unconnected-(SW3-Pad4)") (class "Default")
      (node (ref "SW3") (pin "4") (pinfunction "4_4") (pintype "passive+no_connect"))
    )
    (net (code "54") (name "unconnected-(SW4-Pad2)") (class "Default")
      (node (ref "SW4") (pin "2") (pinfunction "2_2") (pintype "passive+no_connect"))
    )
    (net (code "55") (name "unconnected-(SW4-Pad4)") (class "Default")
      (node (ref "SW4") (pin "4") (pinfunction "4_4") (pintype "passive+no_connect"))
    )
    (net (code "56") (name "unconnected-(SW5-Pad2)") (class "Default")
      (node (ref "SW5") (pin "2") (pinfunction "2_2") (pintype "passive+no_connect"))
    )
    (net (code "57") (name "unconnected-(SW5-Pad4)") (class "Default")
      (node (ref "SW5") (pin "4") (pinfunction "4_4") (pintype "passive+no_connect"))
    )
    (net (code "58") (name "unconnected-(U1-PA1-Pad12)") (class "Default")
      (node (ref "U1") (pin "12") (pinfunction "PA1_12") (pintype "passive"))
    )
    (net (code "59") (name "unconnected-(U1-PA3-Pad14)") (class "Default")
      (node (ref "U1") (pin "14") (pinfunction "PA3_14") (pintype "passive"))
    )
    (net (code "60") (name "unconnected-(U1-PA5-Pad16)") (class "Default")
      (node (ref "U1") (pin "16") (pinfunction "PA5_16") (pintype "passive"))
    )
    (net (code "61") (name "unconnected-(U1-PA6-Pad17)") (class "Default")
      (node (ref "U1") (pin "17") (pinfunction "PA6_17") (pintype "passive"))
    )
    (net (code "62") (name "unconnected-(U1-PA7-Pad18)") (class "Default")
      (node (ref "U1") (pin "18") (pinfunction "PA7_18") (pintype "passive"))
    )
    (net (code "63") (name "unconnected-(U1-PB0-Pad19)") (class "Default")
      (node (ref "U1") (pin "19") (pinfunction "PB0_19") (pintype "passive"))
    )
    (net (code "64") (name "unconnected-(U1-PB1-Pad20)") (class "Default")
      (node (ref "U1") (pin "20") (pinfunction "PB1_20") (pintype "passive"))
    )
    (net (code "65") (name "unconnected-(U1-PB2-Pad21)") (class "Default")
      (node (ref "U1") (pin "21") (pinfunction "PB2_21") (pintype "passive"))
    )
    (net (code "66") (name "unconnected-(U1-PB3-Pad42)") (class "Default")
      (node (ref "U1") (pin "42") (pinfunction "PB3_42") (pintype "passive"))
    )
    (net (code "67") (name "unconnected-(U1-PB4-Pad43)") (class "Default")
      (node (ref "U1") (pin "43") (pinfunction "PB4_43") (pintype "passive"))
    )
    (net (code "68") (name "unconnected-(U1-PB5-Pad44)") (class "Default")
      (node (ref "U1") (pin "44") (pinfunction "PB5_44") (pintype "passive"))
    )
    (net (code "69") (name "unconnected-(U1-PB10-Pad22)") (class "Default")
      (node (ref "U1") (pin "22") (pinfunction "PB10_22") (pintype "passive"))
    )
    (net (code "70") (name "unconnected-(U1-PB11-Pad23)") (class "Default")
      (node (ref "U1") (pin "23") (pinfunction "PB11_23") (pintype "passive"))
    )
    (net (code "71") (name "unconnected-(U1-PB12-Pad24)") (class "Default")
      (node (ref "U1") (pin "24") (pinfunction "PB12_24") (pintype "passive"))
    )
    (net (code "72") (name "unconnected-(U1-PB13-Pad25)") (class "Default")
      (node (ref "U1") (pin "25") (pinfunction "PB13_25") (pintype "passive"))
    )
    (net (code "73") (name "unconnected-(U1-PB14-Pad26)") (class "Default")
      (node (ref "U1") (pin "26") (pinfunction "PB14_26") (pintype "passive"))
    )
    (net (code "74") (name "unconnected-(U1-PB15-Pad27)") (class "Default")
      (node (ref "U1") (pin "27") (pinfunction "PB15_27") (pintype "passive"))
    )
    (net (code "75") (name "unconnected-(U1-PF0-OSC_IN-Pad8)") (class "Default")
      (node (ref "U1") (pin "8") (pinfunction "PF0-OSC_IN_8") (pintype "passive"))
    )
    (net (code "76") (name "unconnected-(U1-PF1-OSC_OUT-Pad9)") (class "Default")
      (node (ref "U1") (pin "9") (pinfunction "PF1-OSC_OUT_9") (pintype "passive"))
    )
    (net (code "77") (name "unconnected-(U3-KEY4-Pad9)") (class "Default")
      (node (ref "U3") (pin "9") (pinfunction "KEY4_9") (pintype "passive"))
    )
    (net (code "78") (name "unconnected-(U3-KEY5-Pad8)") (class "Default")
      (node (ref "U3") (pin "8") (pinfunction "KEY5_8") (pintype "passive"))
    )
    (net (code "79") (name "unconnected-(U3-KEY6-Pad7)") (class "Default")
      (node (ref "U3") (pin "7") (pinfunction "KEY6_7") (pintype "passive"))
    )
  )
)
